# 10-_RS485.net
KiCad netlist of a schematic drawn in Altium Designer
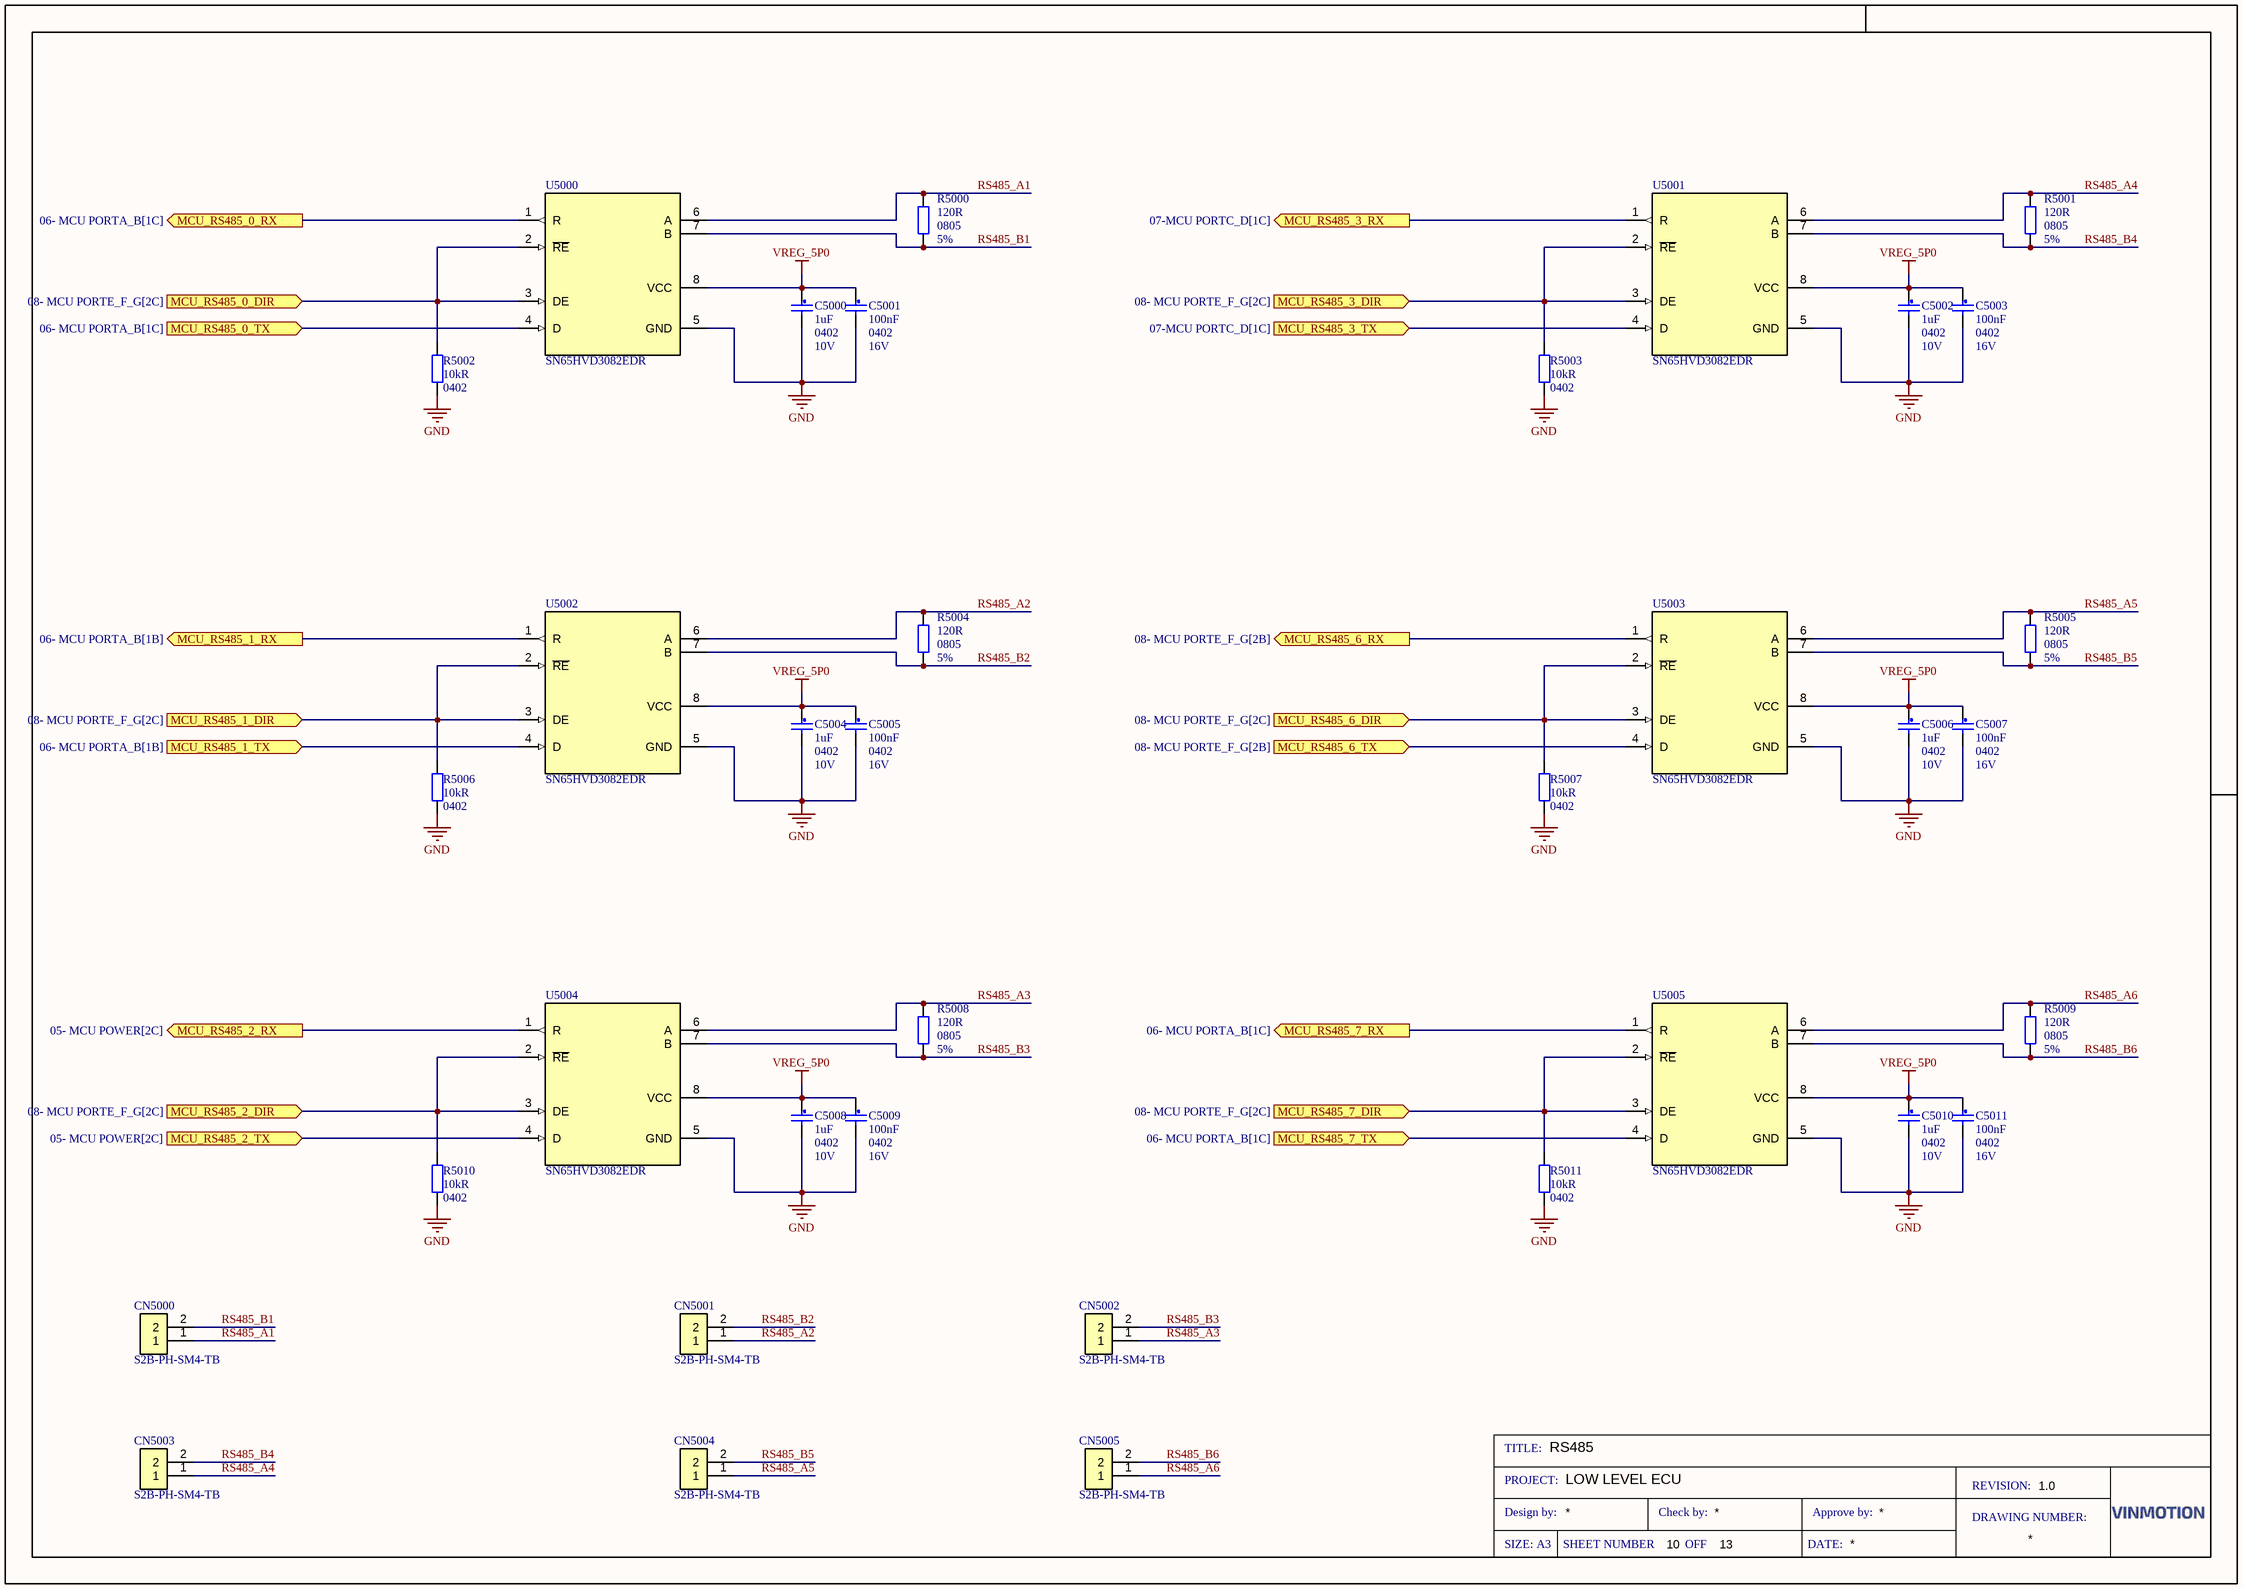
[diagram p0: 10- RS485.SchDoc]

(export (version "E")
  (design (tool "Eeschema 10.0.6"))
  (components
    (comp (ref "C5000")
      (value "1uF")
      (footprint "CAP0402")
      (description "CAP CER 1UF 10V X6S 0402")
      (fields
        (field (name "MANUFACTURER") "Samsung")
        (field (name "MANUFACTURER PART NUMBER") "CL05X105KP5NNNC")
        (field (name "CASE/PACKAGE") "0402")
        (field (name "RATED DC VOLTAGE (URDC)") "10V")
      )
      (libsource (lib "VMO_Lib") (part "CMP-01106-1"))
    )
    (comp (ref "C5001")
      (value "0402YC104KAT2A")
      (footprint "CAP0402")
      (description "CAP CER 0.1UF 16V X7R 0402")
      (fields
        (field (name "CAPACITANCE") "100nF")
        (field (name "CASE/PACKAGE") "0402")
        (field (name "VOLTAGE RATING (DC)") "16V")
      )
      (libsource (lib "VMO_Lib") (part "CMP-00988-1"))
    )
    (comp (ref "C5002")
      (value "1uF")
      (footprint "CAP0402")
      (description "CAP CER 1UF 10V X6S 0402")
      (fields
        (field (name "MANUFACTURER") "Samsung")
        (field (name "MANUFACTURER PART NUMBER") "CL05X105KP5NNNC")
        (field (name "CASE/PACKAGE") "0402")
        (field (name "RATED DC VOLTAGE (URDC)") "10V")
      )
      (libsource (lib "VMO_Lib") (part "CMP-01106-1"))
    )
    (comp (ref "C5003")
      (value "0402YC104KAT2A")
      (footprint "CAP0402")
      (description "CAP CER 0.1UF 16V X7R 0402")
      (fields
        (field (name "CAPACITANCE") "100nF")
        (field (name "CASE/PACKAGE") "0402")
        (field (name "VOLTAGE RATING (DC)") "16V")
      )
      (libsource (lib "VMO_Lib") (part "CMP-00988-1"))
    )
    (comp (ref "C5004")
      (value "1uF")
      (footprint "CAP0402")
      (description "CAP CER 1UF 10V X6S 0402")
      (fields
        (field (name "MANUFACTURER") "Samsung")
        (field (name "MANUFACTURER PART NUMBER") "CL05X105KP5NNNC")
        (field (name "CASE/PACKAGE") "0402")
        (field (name "RATED DC VOLTAGE (URDC)") "10V")
      )
      (libsource (lib "VMO_Lib") (part "CMP-01106-1"))
    )
    (comp (ref "C5005")
      (value "0402YC104KAT2A")
      (footprint "CAP0402")
      (description "CAP CER 0.1UF 16V X7R 0402")
      (fields
        (field (name "CAPACITANCE") "100nF")
        (field (name "CASE/PACKAGE") "0402")
        (field (name "VOLTAGE RATING (DC)") "16V")
      )
      (libsource (lib "VMO_Lib") (part "CMP-00988-1"))
    )
    (comp (ref "C5006")
      (value "1uF")
      (footprint "CAP0402")
      (description "CAP CER 1UF 10V X6S 0402")
      (fields
        (field (name "MANUFACTURER") "Samsung")
        (field (name "MANUFACTURER PART NUMBER") "CL05X105KP5NNNC")
        (field (name "CASE/PACKAGE") "0402")
        (field (name "RATED DC VOLTAGE (URDC)") "10V")
      )
      (libsource (lib "VMO_Lib") (part "CMP-01106-1"))
    )
    (comp (ref "C5007")
      (value "0402YC104KAT2A")
      (footprint "CAP0402")
      (description "CAP CER 0.1UF 16V X7R 0402")
      (fields
        (field (name "CAPACITANCE") "100nF")
        (field (name "CASE/PACKAGE") "0402")
        (field (name "VOLTAGE RATING (DC)") "16V")
      )
      (libsource (lib "VMO_Lib") (part "CMP-00988-1"))
    )
    (comp (ref "C5008")
      (value "1uF")
      (footprint "CAP0402")
      (description "CAP CER 1UF 10V X6S 0402")
      (fields
        (field (name "MANUFACTURER") "Samsung")
        (field (name "MANUFACTURER PART NUMBER") "CL05X105KP5NNNC")
        (field (name "CASE/PACKAGE") "0402")
        (field (name "RATED DC VOLTAGE (URDC)") "10V")
      )
      (libsource (lib "VMO_Lib") (part "CMP-01106-1"))
    )
    (comp (ref "C5009")
      (value "0402YC104KAT2A")
      (footprint "CAP0402")
      (description "CAP CER 0.1UF 16V X7R 0402")
      (fields
        (field (name "CAPACITANCE") "100nF")
        (field (name "CASE/PACKAGE") "0402")
        (field (name "VOLTAGE RATING (DC)") "16V")
      )
      (libsource (lib "VMO_Lib") (part "CMP-00988-1"))
    )
    (comp (ref "C5010")
      (value "1uF")
      (footprint "CAP0402")
      (description "CAP CER 1UF 10V X6S 0402")
      (fields
        (field (name "MANUFACTURER") "Samsung")
        (field (name "MANUFACTURER PART NUMBER") "CL05X105KP5NNNC")
        (field (name "CASE/PACKAGE") "0402")
        (field (name "RATED DC VOLTAGE (URDC)") "10V")
      )
      (libsource (lib "VMO_Lib") (part "CMP-01106-1"))
    )
    (comp (ref "C5011")
      (value "0402YC104KAT2A")
      (footprint "CAP0402")
      (description "CAP CER 0.1UF 16V X7R 0402")
      (fields
        (field (name "CAPACITANCE") "100nF")
        (field (name "CASE/PACKAGE") "0402")
        (field (name "VOLTAGE RATING (DC)") "16V")
      )
      (libsource (lib "VMO_Lib") (part "CMP-00988-1"))
    )
    (comp (ref "CN5000")
      (value "S2B-PH-SM4-TB")
      (footprint "S2B-PH-SM4-TB")
      (description "CONN HEADER SMD R/A 2POS 2MM")
      (fields (field (name "MANUFACTURER") "JST") (field (name "MANUFACTURER PART NUMBER") "S2BPHSM4TBLFSN"))
      (libsource (lib "VMO_Lib") (part "CMP-01142-1"))
    )
    (comp (ref "CN5001")
      (value "S2B-PH-SM4-TB")
      (footprint "S2B-PH-SM4-TB")
      (description "CONN HEADER SMD R/A 2POS 2MM")
      (fields (field (name "MANUFACTURER") "JST") (field (name "MANUFACTURER PART NUMBER") "S2BPHSM4TBLFSN"))
      (libsource (lib "VMO_Lib") (part "CMP-01142-1"))
    )
    (comp (ref "CN5002")
      (value "S2B-PH-SM4-TB")
      (footprint "S2B-PH-SM4-TB")
      (description "CONN HEADER SMD R/A 2POS 2MM")
      (fields (field (name "MANUFACTURER") "JST") (field (name "MANUFACTURER PART NUMBER") "S2BPHSM4TBLFSN"))
      (libsource (lib "VMO_Lib") (part "CMP-01142-1"))
    )
    (comp (ref "CN5003")
      (value "S2B-PH-SM4-TB")
      (footprint "S2B-PH-SM4-TB")
      (description "CONN HEADER SMD R/A 2POS 2MM")
      (fields (field (name "MANUFACTURER") "JST") (field (name "MANUFACTURER PART NUMBER") "S2BPHSM4TBLFSN"))
      (libsource (lib "VMO_Lib") (part "CMP-01142-1"))
    )
    (comp (ref "CN5004")
      (value "S2B-PH-SM4-TB")
      (footprint "S2B-PH-SM4-TB")
      (description "CONN HEADER SMD R/A 2POS 2MM")
      (fields (field (name "MANUFACTURER") "JST") (field (name "MANUFACTURER PART NUMBER") "S2BPHSM4TBLFSN"))
      (libsource (lib "VMO_Lib") (part "CMP-01142-1"))
    )
    (comp (ref "CN5005")
      (value "S2B-PH-SM4-TB")
      (footprint "S2B-PH-SM4-TB")
      (description "CONN HEADER SMD R/A 2POS 2MM")
      (fields (field (name "MANUFACTURER") "JST") (field (name "MANUFACTURER PART NUMBER") "S2BPHSM4TBLFSN"))
      (libsource (lib "VMO_Lib") (part "CMP-01142-1"))
    )
    (comp (ref "R5000")
      (value "120R")
      (footprint "RES0805")
      (description "RES SMD 120 OHM 5% 1/2W 0805")
      (fields
        (field (name "MANUFACTURER") "Panasonic")
        (field (name "MANUFACTURER PART NUMBER") "ERJ-P06J121V")
        (field (name "CASE/PACKAGE") "0805")
        (field (name "TOLERANCE") "5%")
      )
      (libsource (lib "VMO_Lib") (part "CMP-01121-1"))
    )
    (comp (ref "R5001")
      (value "120R")
      (footprint "RES0805")
      (description "RES SMD 120 OHM 5% 1/2W 0805")
      (fields
        (field (name "MANUFACTURER") "Panasonic")
        (field (name "MANUFACTURER PART NUMBER") "ERJ-P06J121V")
        (field (name "CASE/PACKAGE") "0805")
        (field (name "TOLERANCE") "5%")
      )
      (libsource (lib "VMO_Lib") (part "CMP-01121-1"))
    )
    (comp (ref "R5002")
      (value "ERJ2GEJ103X")
      (footprint "RES0402")
      (description "RES SMD 10K OHM 5% 1/10W 0402")
      (fields
        (field (name "TOLERANCE") "5%")
        (field (name "RESISTANCE") "10kR")
        (field (name "CASE/PACKAGE") "0402")
      )
      (libsource (lib "VMO_Lib") (part "CMP-00039-6"))
    )
    (comp (ref "R5003")
      (value "ERJ2GEJ103X")
      (footprint "RES0402")
      (description "RES SMD 10K OHM 5% 1/10W 0402")
      (fields
        (field (name "TOLERANCE") "5%")
        (field (name "RESISTANCE") "10kR")
        (field (name "CASE/PACKAGE") "0402")
      )
      (libsource (lib "VMO_Lib") (part "CMP-00039-6"))
    )
    (comp (ref "R5004")
      (value "120R")
      (footprint "RES0805")
      (description "RES SMD 120 OHM 5% 1/2W 0805")
      (fields
        (field (name "MANUFACTURER") "Panasonic")
        (field (name "MANUFACTURER PART NUMBER") "ERJ-P06J121V")
        (field (name "CASE/PACKAGE") "0805")
        (field (name "TOLERANCE") "5%")
      )
      (libsource (lib "VMO_Lib") (part "CMP-01121-1"))
    )
    (comp (ref "R5005")
      (value "120R")
      (footprint "RES0805")
      (description "RES SMD 120 OHM 5% 1/2W 0805")
      (fields
        (field (name "MANUFACTURER") "Panasonic")
        (field (name "MANUFACTURER PART NUMBER") "ERJ-P06J121V")
        (field (name "CASE/PACKAGE") "0805")
        (field (name "TOLERANCE") "5%")
      )
      (libsource (lib "VMO_Lib") (part "CMP-01121-1"))
    )
    (comp (ref "R5006")
      (value "ERJ2GEJ103X")
      (footprint "RES0402")
      (description "RES SMD 10K OHM 5% 1/10W 0402")
      (fields
        (field (name "TOLERANCE") "5%")
        (field (name "RESISTANCE") "10kR")
        (field (name "CASE/PACKAGE") "0402")
      )
      (libsource (lib "VMO_Lib") (part "CMP-00039-6"))
    )
    (comp (ref "R5007")
      (value "ERJ2GEJ103X")
      (footprint "RES0402")
      (description "RES SMD 10K OHM 5% 1/10W 0402")
      (fields
        (field (name "TOLERANCE") "5%")
        (field (name "RESISTANCE") "10kR")
        (field (name "CASE/PACKAGE") "0402")
      )
      (libsource (lib "VMO_Lib") (part "CMP-00039-6"))
    )
    (comp (ref "R5008")
      (value "120R")
      (footprint "RES0805")
      (description "RES SMD 120 OHM 5% 1/2W 0805")
      (fields
        (field (name "MANUFACTURER") "Panasonic")
        (field (name "MANUFACTURER PART NUMBER") "ERJ-P06J121V")
        (field (name "CASE/PACKAGE") "0805")
        (field (name "TOLERANCE") "5%")
      )
      (libsource (lib "VMO_Lib") (part "CMP-01121-1"))
    )
    (comp (ref "R5009")
      (value "120R")
      (footprint "RES0805")
      (description "RES SMD 120 OHM 5% 1/2W 0805")
      (fields
        (field (name "MANUFACTURER") "Panasonic")
        (field (name "MANUFACTURER PART NUMBER") "ERJ-P06J121V")
        (field (name "CASE/PACKAGE") "0805")
        (field (name "TOLERANCE") "5%")
      )
      (libsource (lib "VMO_Lib") (part "CMP-01121-1"))
    )
    (comp (ref "R5010")
      (value "ERJ2GEJ103X")
      (footprint "RES0402")
      (description "RES SMD 10K OHM 5% 1/10W 0402")
      (fields
        (field (name "TOLERANCE") "5%")
        (field (name "RESISTANCE") "10kR")
        (field (name "CASE/PACKAGE") "0402")
      )
      (libsource (lib "VMO_Lib") (part "CMP-00039-6"))
    )
    (comp (ref "R5011")
      (value "ERJ2GEJ103X")
      (footprint "RES0402")
      (description "RES SMD 10K OHM 5% 1/10W 0402")
      (fields
        (field (name "TOLERANCE") "5%")
        (field (name "RESISTANCE") "10kR")
        (field (name "CASE/PACKAGE") "0402")
      )
      (libsource (lib "VMO_Lib") (part "CMP-00039-6"))
    )
    (comp (ref "U5000")
      (value "SN65HVD3082EDR")
      (footprint "SOIC127P590X175-8N")
      (description "IC TRANSCEIVER HALF 1/1 8SOIC")
      (fields (field (name "MANUFACTURER") "Texas Instruments"))
      (libsource (lib "VMO_Lib") (part "CMP-01120-1"))
    )
    (comp (ref "U5001")
      (value "SN65HVD3082EDR")
      (footprint "SOIC127P590X175-8N")
      (description "IC TRANSCEIVER HALF 1/1 8SOIC")
      (fields (field (name "MANUFACTURER") "Texas Instruments"))
      (libsource (lib "VMO_Lib") (part "CMP-01120-1"))
    )
    (comp (ref "U5002")
      (value "SN65HVD3082EDR")
      (footprint "SOIC127P590X175-8N")
      (description "IC TRANSCEIVER HALF 1/1 8SOIC")
      (fields (field (name "MANUFACTURER") "Texas Instruments"))
      (libsource (lib "VMO_Lib") (part "CMP-01120-1"))
    )
    (comp (ref "U5003")
      (value "SN65HVD3082EDR")
      (footprint "SOIC127P590X175-8N")
      (description "IC TRANSCEIVER HALF 1/1 8SOIC")
      (fields (field (name "MANUFACTURER") "Texas Instruments"))
      (libsource (lib "VMO_Lib") (part "CMP-01120-1"))
    )
    (comp (ref "U5004")
      (value "SN65HVD3082EDR")
      (footprint "SOIC127P590X175-8N")
      (description "IC TRANSCEIVER HALF 1/1 8SOIC")
      (fields (field (name "MANUFACTURER") "Texas Instruments"))
      (libsource (lib "VMO_Lib") (part "CMP-01120-1"))
    )
    (comp (ref "U5005")
      (value "SN65HVD3082EDR")
      (footprint "SOIC127P590X175-8N")
      (description "IC TRANSCEIVER HALF 1/1 8SOIC")
      (fields (field (name "MANUFACTURER") "Texas Instruments"))
      (libsource (lib "VMO_Lib") (part "CMP-01120-1"))
    )
  )
  (nets
    (net (code "1") (name "/MCU_RS485_0_DIR") (class "Default")
      (node (ref "R5002") (pin "2") (pinfunction "2_2") (pintype "passive"))
      (node (ref "U5000") (pin "2") (pinfunction "~{RE}_2") (pintype "input"))
      (node (ref "U5000") (pin "3") (pinfunction "DE_3") (pintype "input"))
    )
    (net (code "2") (name "/MCU_RS485_0_RX") (class "Default")
      (node (ref "U5000") (pin "1") (pinfunction "R_1") (pintype "output"))
    )
    (net (code "3") (name "/MCU_RS485_0_TX") (class "Default")
      (node (ref "U5000") (pin "4") (pinfunction "D_4") (pintype "input"))
    )
    (net (code "4") (name "/MCU_RS485_1_DIR") (class "Default")
      (node (ref "R5006") (pin "2") (pinfunction "2_2") (pintype "passive"))
      (node (ref "U5002") (pin "2") (pinfunction "~{RE}_2") (pintype "input"))
      (node (ref "U5002") (pin "3") (pinfunction "DE_3") (pintype "input"))
    )
    (net (code "5") (name "/MCU_RS485_1_RX") (class "Default")
      (node (ref "U5002") (pin "1") (pinfunction "R_1") (pintype "output"))
    )
    (net (code "6") (name "/MCU_RS485_1_TX") (class "Default")
      (node (ref "U5002") (pin "4") (pinfunction "D_4") (pintype "input"))
    )
    (net (code "7") (name "/MCU_RS485_2_DIR") (class "Default")
      (node (ref "R5010") (pin "2") (pinfunction "2_2") (pintype "passive"))
      (node (ref "U5004") (pin "2") (pinfunction "~{RE}_2") (pintype "input"))
      (node (ref "U5004") (pin "3") (pinfunction "DE_3") (pintype "input"))
    )
    (net (code "8") (name "/MCU_RS485_2_RX") (class "Default")
      (node (ref "U5004") (pin "1") (pinfunction "R_1") (pintype "output"))
    )
    (net (code "9") (name "/MCU_RS485_2_TX") (class "Default")
      (node (ref "U5004") (pin "4") (pinfunction "D_4") (pintype "input"))
    )
    (net (code "10") (name "/MCU_RS485_3_DIR") (class "Default")
      (node (ref "R5003") (pin "2") (pinfunction "2_2") (pintype "passive"))
      (node (ref "U5001") (pin "2") (pinfunction "~{RE}_2") (pintype "input"))
      (node (ref "U5001") (pin "3") (pinfunction "DE_3") (pintype "input"))
    )
    (net (code "11") (name "/MCU_RS485_3_RX") (class "Default")
      (node (ref "U5001") (pin "1") (pinfunction "R_1") (pintype "output"))
    )
    (net (code "12") (name "/MCU_RS485_3_TX") (class "Default")
      (node (ref "U5001") (pin "4") (pinfunction "D_4") (pintype "input"))
    )
    (net (code "13") (name "/MCU_RS485_6_DIR") (class "Default")
      (node (ref "R5007") (pin "2") (pinfunction "2_2") (pintype "passive"))
      (node (ref "U5003") (pin "2") (pinfunction "~{RE}_2") (pintype "input"))
      (node (ref "U5003") (pin "3") (pinfunction "DE_3") (pintype "input"))
    )
    (net (code "14") (name "/MCU_RS485_6_RX") (class "Default")
      (node (ref "U5003") (pin "1") (pinfunction "R_1") (pintype "output"))
    )
    (net (code "15") (name "/MCU_RS485_6_TX") (class "Default")
      (node (ref "U5003") (pin "4") (pinfunction "D_4") (pintype "input"))
    )
    (net (code "16") (name "/MCU_RS485_7_DIR") (class "Default")
      (node (ref "R5011") (pin "2") (pinfunction "2_2") (pintype "passive"))
      (node (ref "U5005") (pin "2") (pinfunction "~{RE}_2") (pintype "input"))
      (node (ref "U5005") (pin "3") (pinfunction "DE_3") (pintype "input"))
    )
    (net (code "17") (name "/MCU_RS485_7_RX") (class "Default")
      (node (ref "U5005") (pin "1") (pinfunction "R_1") (pintype "output"))
    )
    (net (code "18") (name "/MCU_RS485_7_TX") (class "Default")
      (node (ref "U5005") (pin "4") (pinfunction "D_4") (pintype "input"))
    )
    (net (code "19") (name "/RS485_A1") (class "Default")
      (node (ref "CN5000") (pin "1") (pinfunction "1_1") (pintype "passive"))
      (node (ref "R5000") (pin "1") (pinfunction "1_1") (pintype "passive"))
      (node (ref "U5000") (pin "6") (pinfunction "A_6") (pintype "passive"))
    )
    (net (code "20") (name "/RS485_A2") (class "Default")
      (node (ref "CN5001") (pin "1") (pinfunction "1_1") (pintype "passive"))
      (node (ref "R5004") (pin "1") (pinfunction "1_1") (pintype "passive"))
      (node (ref "U5002") (pin "6") (pinfunction "A_6") (pintype "passive"))
    )
    (net (code "21") (name "/RS485_A3") (class "Default")
      (node (ref "CN5002") (pin "1") (pinfunction "1_1") (pintype "passive"))
      (node (ref "R5008") (pin "1") (pinfunction "1_1") (pintype "passive"))
      (node (ref "U5004") (pin "6") (pinfunction "A_6") (pintype "passive"))
    )
    (net (code "22") (name "/RS485_A4") (class "Default")
      (node (ref "CN5003") (pin "1") (pinfunction "1_1") (pintype "passive"))
      (node (ref "R5001") (pin "1") (pinfunction "1_1") (pintype "passive"))
      (node (ref "U5001") (pin "6") (pinfunction "A_6") (pintype "passive"))
    )
    (net (code "23") (name "/RS485_A5") (class "Default")
      (node (ref "CN5004") (pin "1") (pinfunction "1_1") (pintype "passive"))
      (node (ref "R5005") (pin "1") (pinfunction "1_1") (pintype "passive"))
      (node (ref "U5003") (pin "6") (pinfunction "A_6") (pintype "passive"))
    )
    (net (code "24") (name "/RS485_A6") (class "Default")
      (node (ref "CN5005") (pin "1") (pinfunction "1_1") (pintype "passive"))
      (node (ref "R5009") (pin "1") (pinfunction "1_1") (pintype "passive"))
      (node (ref "U5005") (pin "6") (pinfunction "A_6") (pintype "passive"))
    )
    (net (code "25") (name "/RS485_B1") (class "Default")
      (node (ref "CN5000") (pin "2") (pinfunction "2_2") (pintype "passive"))
      (node (ref "R5000") (pin "2") (pinfunction "2_2") (pintype "passive"))
      (node (ref "U5000") (pin "7") (pinfunction "B_7") (pintype "passive"))
    )
    (net (code "26") (name "/RS485_B2") (class "Default")
      (node (ref "CN5001") (pin "2") (pinfunction "2_2") (pintype "passive"))
      (node (ref "R5004") (pin "2") (pinfunction "2_2") (pintype "passive"))
      (node (ref "U5002") (pin "7") (pinfunction "B_7") (pintype "passive"))
    )
    (net (code "27") (name "/RS485_B3") (class "Default")
      (node (ref "CN5002") (pin "2") (pinfunction "2_2") (pintype "passive"))
      (node (ref "R5008") (pin "2") (pinfunction "2_2") (pintype "passive"))
      (node (ref "U5004") (pin "7") (pinfunction "B_7") (pintype "passive"))
    )
    (net (code "28") (name "/RS485_B4") (class "Default")
      (node (ref "CN5003") (pin "2") (pinfunction "2_2") (pintype "passive"))
      (node (ref "R5001") (pin "2") (pinfunction "2_2") (pintype "passive"))
      (node (ref "U5001") (pin "7") (pinfunction "B_7") (pintype "passive"))
    )
    (net (code "29") (name "/RS485_B5") (class "Default")
      (node (ref "CN5004") (pin "2") (pinfunction "2_2") (pintype "passive"))
      (node (ref "R5005") (pin "2") (pinfunction "2_2") (pintype "passive"))
      (node (ref "U5003") (pin "7") (pinfunction "B_7") (pintype "passive"))
    )
    (net (code "30") (name "/RS485_B6") (class "Default")
      (node (ref "CN5005") (pin "2") (pinfunction "2_2") (pintype "passive"))
      (node (ref "R5009") (pin "2") (pinfunction "2_2") (pintype "passive"))
      (node (ref "U5005") (pin "7") (pinfunction "B_7") (pintype "passive"))
    )
    (net (code "31") (name "GND") (class "Default")
      (node (ref "C5000") (pin "2") (pinfunction "2_2") (pintype "passive"))
      (node (ref "C5001") (pin "2") (pinfunction "2_2") (pintype "passive"))
      (node (ref "C5002") (pin "2") (pinfunction "2_2") (pintype "passive"))
      (node (ref "C5003") (pin "2") (pinfunction "2_2") (pintype "passive"))
      (node (ref "C5004") (pin "2") (pinfunction "2_2") (pintype "passive"))
      (node (ref "C5005") (pin "2") (pinfunction "2_2") (pintype "passive"))
      (node (ref "C5006") (pin "2") (pinfunction "2_2") (pintype "passive"))
      (node (ref "C5007") (pin "2") (pinfunction "2_2") (pintype "passive"))
      (node (ref "C5008") (pin "2") (pinfunction "2_2") (pintype "passive"))
      (node (ref "C5009") (pin "2") (pinfunction "2_2") (pintype "passive"))
      (node (ref "C5010") (pin "2") (pinfunction "2_2") (pintype "passive"))
      (node (ref "C5011") (pin "2") (pinfunction "2_2") (pintype "passive"))
      (node (ref "R5002") (pin "1") (pinfunction "1_1") (pintype "passive"))
      (node (ref "R5003") (pin "1") (pinfunction "1_1") (pintype "passive"))
      (node (ref "R5006") (pin "1") (pinfunction "1_1") (pintype "passive"))
      (node (ref "R5007") (pin "1") (pinfunction "1_1") (pintype "passive"))
      (node (ref "R5010") (pin "1") (pinfunction "1_1") (pintype "passive"))
      (node (ref "R5011") (pin "1") (pinfunction "1_1") (pintype "passive"))
      (node (ref "U5000") (pin "5") (pinfunction "GND_5") (pintype "power_in"))
      (node (ref "U5001") (pin "5") (pinfunction "GND_5") (pintype "power_in"))
      (node (ref "U5002") (pin "5") (pinfunction "GND_5") (pintype "power_in"))
      (node (ref "U5003") (pin "5") (pinfunction "GND_5") (pintype "power_in"))
      (node (ref "U5004") (pin "5") (pinfunction "GND_5") (pintype "power_in"))
      (node (ref "U5005") (pin "5") (pinfunction "GND_5") (pintype "power_in"))
    )
    (net (code "32") (name "VREG_5P0") (class "Default")
      (node (ref "C5000") (pin "1") (pinfunction "1_1") (pintype "passive"))
      (node (ref "C5001") (pin "1") (pinfunction "1_1") (pintype "passive"))
      (node (ref "C5002") (pin "1") (pinfunction "1_1") (pintype "passive"))
      (node (ref "C5003") (pin "1") (pinfunction "1_1") (pintype "passive"))
      (node (ref "C5004") (pin "1") (pinfunction "1_1") (pintype "passive"))
      (node (ref "C5005") (pin "1") (pinfunction "1_1") (pintype "passive"))
      (node (ref "C5006") (pin "1") (pinfunction "1_1") (pintype "passive"))
      (node (ref "C5007") (pin "1") (pinfunction "1_1") (pintype "passive"))
      (node (ref "C5008") (pin "1") (pinfunction "1_1") (pintype "passive"))
      (node (ref "C5009") (pin "1") (pinfunction "1_1") (pintype "passive"))
      (node (ref "C5010") (pin "1") (pinfunction "1_1") (pintype "passive"))
      (node (ref "C5011") (pin "1") (pinfunction "1_1") (pintype "passive"))
      (node (ref "U5000") (pin "8") (pinfunction "VCC_8") (pintype "power_in"))
      (node (ref "U5001") (pin "8") (pinfunction "VCC_8") (pintype "power_in"))
      (node (ref "U5002") (pin "8") (pinfunction "VCC_8") (pintype "power_in"))
      (node (ref "U5003") (pin "8") (pinfunction "VCC_8") (pintype "power_in"))
      (node (ref "U5004") (pin "8") (pinfunction "VCC_8") (pintype "power_in"))
      (node (ref "U5005") (pin "8") (pinfunction "VCC_8") (pintype "power_in"))
    )
  )
)
